# Archimedes_Islemci_Kat.net
KiCad netlist of a schematic drawn in Altium Designer
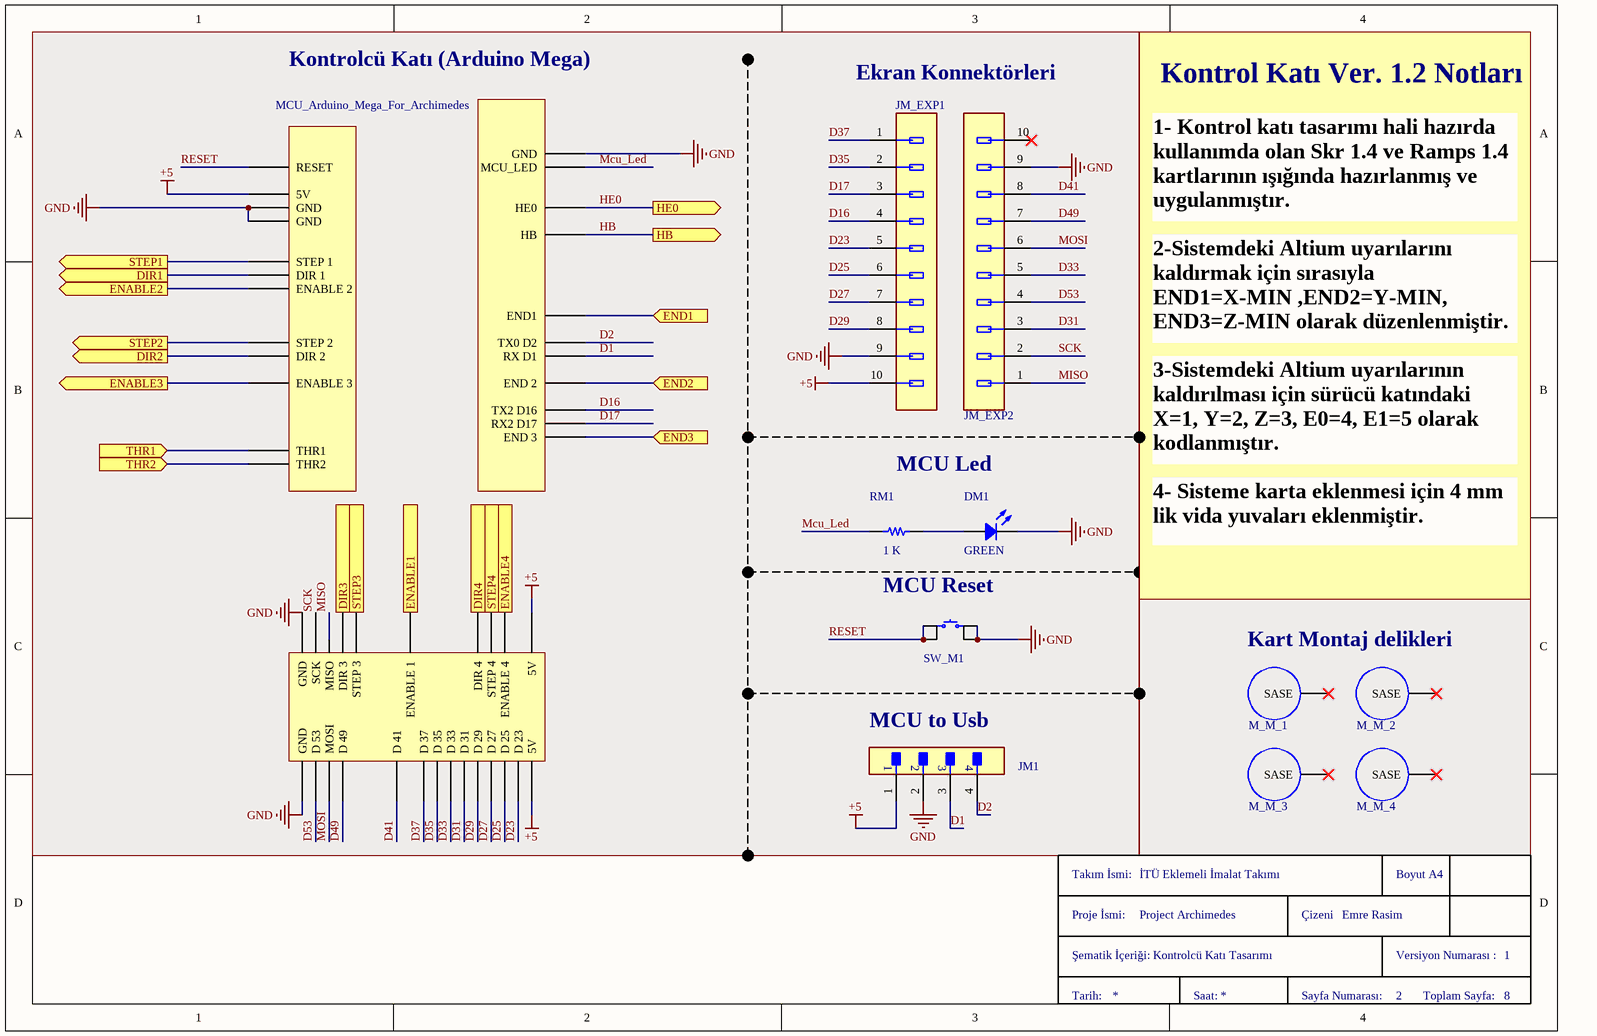
[diagram p0: Archimedes_Islemci_Katı.SchDoc]

(export (version "E")
  (design (tool "Eeschema 10.0.6"))
  (components
    (comp (ref "DM1")
      (value "GREEN")
      (footprint "LED 0805/2012 GREEN")
      (description "LED 805")
      (libsource (lib "Pasifler") (part "LED 805"))
    )
    (comp (ref "JM1")
      (value "2.5 mm locked")
      (footprint "CON_2.5MM_4_LEAD_180_LOCKED")
      (description "2.5 mm 4 lead locked connector")
      (libsource (lib "EKIM_Team_Main") (part "Con_2.5mm_4_lead_180_locked"))
    )
    (comp (ref "JM_EXP1")
      (value "Con_2.54mm_10 lead_2 row_Ipc connector")
      (footprint "Con_10pin_2row_ıpc_connector")
      (description "CONN 10 Positions Header Connector 0.100\" (2.54mm) Through Hole Gold")
      (fields (field (name "VOLTAGE") "250V") (field (name "MANUFACTURER") "Molex"))
      (libsource (lib "") (part "Con_2.54mm_10 lead_2 row_Ipc connector_1"))
    )
    (comp (ref "JM_EXP2")
      (value "Con_2.54mm_10 lead_2 row_Ipc connector")
      (footprint "Con_10pin_2row_ıpc_connector")
      (description "CONN 10 Positions Header Connector 0.100\" (2.54mm) Through Hole Gold")
      (fields (field (name "VOLTAGE") "250V") (field (name "MANUFACTURER") "Molex"))
      (libsource (lib "EKIM_Team_Main") (part "Con_2.54mm_10 lead_2 row_Ipc connector"))
    )
    (comp (ref "MCU_Arduino_Mega_For_Archimedes")
      (value "Arduino Mega 2560")
      (footprint "MCU_Arduino_MEGA for Archimedes")
      (libsource (lib "EKIM_Team_Main") (part "MCU_Arduino_Mega_For_Archimedes"))
    )
    (comp (ref "M_M_1")
      (value "Vida")
      (footprint "Montaj4mm")
      (description "Montaj Deliği 4mm")
      (libsource (lib "Pasifler") (part "Montaj Deliği 4mm"))
    )
    (comp (ref "M_M_2")
      (value "Vida")
      (footprint "Montaj4mm")
      (description "Montaj Deliği 4mm")
      (libsource (lib "Pasifler") (part "Montaj Deliği 4mm"))
    )
    (comp (ref "M_M_3")
      (value "Vida")
      (footprint "Montaj4mm")
      (description "Montaj Deliği 4mm")
      (libsource (lib "Pasifler") (part "Montaj Deliği 4mm"))
    )
    (comp (ref "M_M_4")
      (value "Vida")
      (footprint "Montaj4mm")
      (description "Montaj Deliği 4mm")
      (libsource (lib "Pasifler") (part "Montaj Deliği 4mm"))
    )
    (comp (ref "RM1")
      (value "1 K")
      (footprint "RES 0805/2012")
      (description "Resistor 805")
      (libsource (lib "Pasifler") (part "Resistor 805"))
    )
    (comp (ref "SW_M1")
      (value "Push button with 6x6 landmark")
      (footprint "SW_PUSH_6X6mm")
      (libsource (lib "EKIM_Team_Main") (part "SW_PUSH_6X6mm"))
    )
  )
  (nets
    (net (code "1") (name "+5") (class "Default")
      (node (ref "JM1") (pin "1") (pinfunction "1_1") (pintype "passive"))
      (node (ref "JM_EXP1") (pin "10") (pinfunction "10_10") (pintype "passive"))
      (node (ref "MCU_Arduino_Mega_For_Archimedes") (pin "1") (pinfunction "5V_1") (pintype "passive"))
      (node (ref "MCU_Arduino_Mega_For_Archimedes") (pin "2") (pinfunction "5V_2") (pintype "passive"))
      (node (ref "MCU_Arduino_Mega_For_Archimedes") (pin "56") (pinfunction "5V_56") (pintype "passive"))
    )
    (net (code "2") (name "/D1") (class "Default")
      (node (ref "JM1") (pin "3") (pinfunction "3_3") (pintype "passive"))
      (node (ref "MCU_Arduino_Mega_For_Archimedes") (pin "69") (pinfunction "RX_D1_69") (pintype "passive"))
    )
    (net (code "3") (name "/D2") (class "Default")
      (node (ref "JM1") (pin "4") (pinfunction "4_4") (pintype "passive"))
      (node (ref "MCU_Arduino_Mega_For_Archimedes") (pin "70") (pinfunction "TX0_D2_70") (pintype "passive"))
    )
    (net (code "4") (name "/D16") (class "Default")
      (node (ref "JM_EXP1") (pin "4") (pinfunction "4_4") (pintype "passive"))
      (node (ref "MCU_Arduino_Mega_For_Archimedes") (pin "66") (pinfunction "TX2_D16_66") (pintype "passive"))
    )
    (net (code "5") (name "/D17") (class "Default")
      (node (ref "JM_EXP1") (pin "3") (pinfunction "3_3") (pintype "passive"))
      (node (ref "MCU_Arduino_Mega_For_Archimedes") (pin "65") (pinfunction "RX2_D17_65") (pintype "passive"))
    )
    (net (code "6") (name "/D23") (class "Default")
      (node (ref "JM_EXP1") (pin "5") (pinfunction "5_5") (pintype "passive"))
      (node (ref "MCU_Arduino_Mega_For_Archimedes") (pin "4") (pinfunction "D_23_4") (pintype "passive"))
    )
    (net (code "7") (name "/D25") (class "Default")
      (node (ref "JM_EXP1") (pin "6") (pinfunction "6_6") (pintype "passive"))
      (node (ref "MCU_Arduino_Mega_For_Archimedes") (pin "6") (pinfunction "D_25_6") (pintype "passive"))
    )
    (net (code "8") (name "/D27") (class "Default")
      (node (ref "JM_EXP1") (pin "7") (pinfunction "7_7") (pintype "passive"))
      (node (ref "MCU_Arduino_Mega_For_Archimedes") (pin "8") (pinfunction "D_27_8") (pintype "passive"))
    )
    (net (code "9") (name "/D29") (class "Default")
      (node (ref "JM_EXP1") (pin "8") (pinfunction "8_8") (pintype "passive"))
      (node (ref "MCU_Arduino_Mega_For_Archimedes") (pin "10") (pinfunction "D_29_10") (pintype "passive"))
    )
    (net (code "10") (name "/D31") (class "Default")
      (node (ref "JM_EXP2") (pin "3") (pinfunction "3_3") (pintype "passive"))
      (node (ref "MCU_Arduino_Mega_For_Archimedes") (pin "12") (pinfunction "D_31_12") (pintype "passive"))
    )
    (net (code "11") (name "/D33") (class "Default")
      (node (ref "JM_EXP2") (pin "5") (pinfunction "5_5") (pintype "passive"))
      (node (ref "MCU_Arduino_Mega_For_Archimedes") (pin "14") (pinfunction "D_33_14") (pintype "passive"))
    )
    (net (code "12") (name "/D35") (class "Default")
      (node (ref "JM_EXP1") (pin "2") (pinfunction "2_2") (pintype "passive"))
      (node (ref "MCU_Arduino_Mega_For_Archimedes") (pin "16") (pinfunction "D_35_16") (pintype "passive"))
    )
    (net (code "13") (name "/D37") (class "Default")
      (node (ref "JM_EXP1") (pin "1") (pinfunction "1_1") (pintype "passive"))
      (node (ref "MCU_Arduino_Mega_For_Archimedes") (pin "18") (pinfunction "D_37_18") (pintype "passive"))
    )
    (net (code "14") (name "/D41") (class "Default")
      (node (ref "JM_EXP2") (pin "8") (pinfunction "8_8") (pintype "passive"))
      (node (ref "MCU_Arduino_Mega_For_Archimedes") (pin "22") (pinfunction "D_41_22") (pintype "passive"))
    )
    (net (code "15") (name "/D49") (class "Default")
      (node (ref "JM_EXP2") (pin "7") (pinfunction "7_7") (pintype "passive"))
      (node (ref "MCU_Arduino_Mega_For_Archimedes") (pin "30") (pinfunction "D_49_30") (pintype "passive"))
    )
    (net (code "16") (name "/D53") (class "Default")
      (node (ref "JM_EXP2") (pin "4") (pinfunction "4_4") (pintype "passive"))
      (node (ref "MCU_Arduino_Mega_For_Archimedes") (pin "34") (pinfunction "D_53_34") (pintype "passive"))
    )
    (net (code "17") (name "/DIR1") (class "Default")
      (node (ref "MCU_Arduino_Mega_For_Archimedes") (pin "51") (pinfunction "DIR_1_51") (pintype "passive"))
    )
    (net (code "18") (name "/DIR2") (class "Default")
      (node (ref "MCU_Arduino_Mega_For_Archimedes") (pin "45") (pinfunction "DIR_2_45") (pintype "passive"))
    )
    (net (code "19") (name "/DIR3") (class "Default")
      (node (ref "MCU_Arduino_Mega_For_Archimedes") (pin "29") (pinfunction "DIR_3_29") (pintype "passive"))
    )
    (net (code "20") (name "/DIR4") (class "Default")
      (node (ref "MCU_Arduino_Mega_For_Archimedes") (pin "9") (pinfunction "DIR_4_9") (pintype "passive"))
    )
    (net (code "21") (name "/ENABLE1") (class "Default")
      (node (ref "MCU_Arduino_Mega_For_Archimedes") (pin "19") (pinfunction "ENABLE_1_19") (pintype "passive"))
    )
    (net (code "22") (name "/ENABLE2") (class "Default")
      (node (ref "MCU_Arduino_Mega_For_Archimedes") (pin "50") (pinfunction "ENABLE_2_50") (pintype "passive"))
    )
    (net (code "23") (name "/ENABLE3") (class "Default")
      (node (ref "MCU_Arduino_Mega_For_Archimedes") (pin "44") (pinfunction "ENABLE_3_44") (pintype "passive"))
    )
    (net (code "24") (name "/ENABLE4") (class "Default")
      (node (ref "MCU_Arduino_Mega_For_Archimedes") (pin "5") (pinfunction "ENABLE_4_5") (pintype "passive"))
    )
    (net (code "25") (name "/END1") (class "Default")
      (node (ref "MCU_Arduino_Mega_For_Archimedes") (pin "72") (pinfunction "END1_72") (pintype "passive"))
    )
    (net (code "26") (name "/END2") (class "Default")
      (node (ref "MCU_Arduino_Mega_For_Archimedes") (pin "68") (pinfunction "END_2_68") (pintype "passive"))
    )
    (net (code "27") (name "/END3") (class "Default")
      (node (ref "MCU_Arduino_Mega_For_Archimedes") (pin "64") (pinfunction "END_3_64") (pintype "passive"))
    )
    (net (code "28") (name "/HB") (class "Default")
      (node (ref "MCU_Arduino_Mega_For_Archimedes") (pin "77") (pinfunction "HB_77") (pintype "passive"))
    )
    (net (code "29") (name "/HE0") (class "Default")
      (node (ref "MCU_Arduino_Mega_For_Archimedes") (pin "79") (pinfunction "HE0_79") (pintype "passive"))
    )
    (net (code "30") (name "/MISO") (class "Default")
      (node (ref "JM_EXP2") (pin "1") (pinfunction "1_1") (pintype "passive"))
      (node (ref "MCU_Arduino_Mega_For_Archimedes") (pin "31") (pinfunction "MISO_31") (pintype "passive"))
    )
    (net (code "31") (name "/MOSI") (class "Default")
      (node (ref "JM_EXP2") (pin "6") (pinfunction "6_6") (pintype "passive"))
      (node (ref "MCU_Arduino_Mega_For_Archimedes") (pin "32") (pinfunction "MOSI_32") (pintype "passive"))
    )
    (net (code "32") (name "/Mcu_Led") (class "Default")
      (node (ref "MCU_Arduino_Mega_For_Archimedes") (pin "82") (pinfunction "MCU_LED_82") (pintype "passive"))
      (node (ref "RM1") (pin "1") (pinfunction "1_1") (pintype "passive"))
    )
    (net (code "33") (name "/RESET") (class "Default")
      (node (ref "MCU_Arduino_Mega_For_Archimedes") (pin "58") (pinfunction "RESET_58") (pintype "passive"))
      (node (ref "SW_M1") (pin "1") (pinfunction "1_1") (pintype "passive"))
      (node (ref "SW_M1") (pin "2") (pinfunction "2_2") (pintype "passive"))
    )
    (net (code "34") (name "/SCK") (class "Default")
      (node (ref "JM_EXP2") (pin "2") (pinfunction "2_2") (pintype "passive"))
      (node (ref "MCU_Arduino_Mega_For_Archimedes") (pin "33") (pinfunction "SCK_33") (pintype "passive"))
    )
    (net (code "35") (name "/STEP1") (class "Default")
      (node (ref "MCU_Arduino_Mega_For_Archimedes") (pin "52") (pinfunction "STEP_1_52") (pintype "passive"))
    )
    (net (code "36") (name "/STEP2") (class "Default")
      (node (ref "MCU_Arduino_Mega_For_Archimedes") (pin "46") (pinfunction "STEP_2_46") (pintype "passive"))
    )
    (net (code "37") (name "/STEP3") (class "Default")
      (node (ref "MCU_Arduino_Mega_For_Archimedes") (pin "27") (pinfunction "STEP_3_27") (pintype "passive"))
    )
    (net (code "38") (name "/STEP4") (class "Default")
      (node (ref "MCU_Arduino_Mega_For_Archimedes") (pin "7") (pinfunction "STEP_4_7") (pintype "passive"))
    )
    (net (code "39") (name "/THR1") (class "Default")
      (node (ref "MCU_Arduino_Mega_For_Archimedes") (pin "39") (pinfunction "THR1_39") (pintype "passive"))
    )
    (net (code "40") (name "/THR2") (class "Default")
      (node (ref "MCU_Arduino_Mega_For_Archimedes") (pin "38") (pinfunction "THR2_38") (pintype "passive"))
    )
    (net (code "41") (name "GND") (class "Default")
      (node (ref "DM1") (pin "2") (pinfunction "2_2") (pintype "passive"))
      (node (ref "JM1") (pin "2") (pinfunction "2_2") (pintype "passive"))
      (node (ref "JM_EXP1") (pin "9") (pinfunction "9_9") (pintype "passive"))
      (node (ref "JM_EXP2") (pin "9") (pinfunction "9_9") (pintype "passive"))
      (node (ref "MCU_Arduino_Mega_For_Archimedes") (pin "35") (pinfunction "GND_35") (pintype "passive"))
      (node (ref "MCU_Arduino_Mega_For_Archimedes") (pin "36") (pinfunction "GND_36") (pintype "passive"))
      (node (ref "MCU_Arduino_Mega_For_Archimedes") (pin "54") (pinfunction "GND_54") (pintype "passive"))
      (node (ref "MCU_Arduino_Mega_For_Archimedes") (pin "55") (pinfunction "GND_55") (pintype "passive"))
      (node (ref "MCU_Arduino_Mega_For_Archimedes") (pin "83") (pinfunction "GND_83") (pintype "passive"))
      (node (ref "SW_M1") (pin "3") (pinfunction "3_3") (pintype "passive"))
      (node (ref "SW_M1") (pin "4") (pinfunction "4_4") (pintype "passive"))
    )
    (net (code "42") (name "Net-(DM1-Pad1)") (class "Default")
      (node (ref "DM1") (pin "1") (pinfunction "1_1") (pintype "passive"))
      (node (ref "RM1") (pin "2") (pinfunction "2_2") (pintype "passive"))
    )
    (net (code "43") (name "unconnected-(JM_EXP2-Pad10)") (class "Default")
      (node (ref "JM_EXP2") (pin "10") (pinfunction "10_10") (pintype "passive+no_connect"))
    )
    (net (code "44") (name "unconnected-(M_M_1-SASE-Pad1)") (class "Default")
      (node (ref "M_M_1") (pin "1") (pinfunction "SASE_1") (pintype "passive+no_connect"))
    )
    (net (code "45") (name "unconnected-(M_M_2-SASE-Pad1)") (class "Default")
      (node (ref "M_M_2") (pin "1") (pinfunction "SASE_1") (pintype "passive+no_connect"))
    )
    (net (code "46") (name "unconnected-(M_M_3-SASE-Pad1)") (class "Default")
      (node (ref "M_M_3") (pin "1") (pinfunction "SASE_1") (pintype "passive+no_connect"))
    )
    (net (code "47") (name "unconnected-(M_M_4-SASE-Pad1)") (class "Default")
      (node (ref "M_M_4") (pin "1") (pinfunction "SASE_1") (pintype "passive+no_connect"))
    )
  )
)
